# ProPrj_usb__2025-12-14-12-39-50.net
KiCad netlist of a schematic drawn in EasyEDA Pro
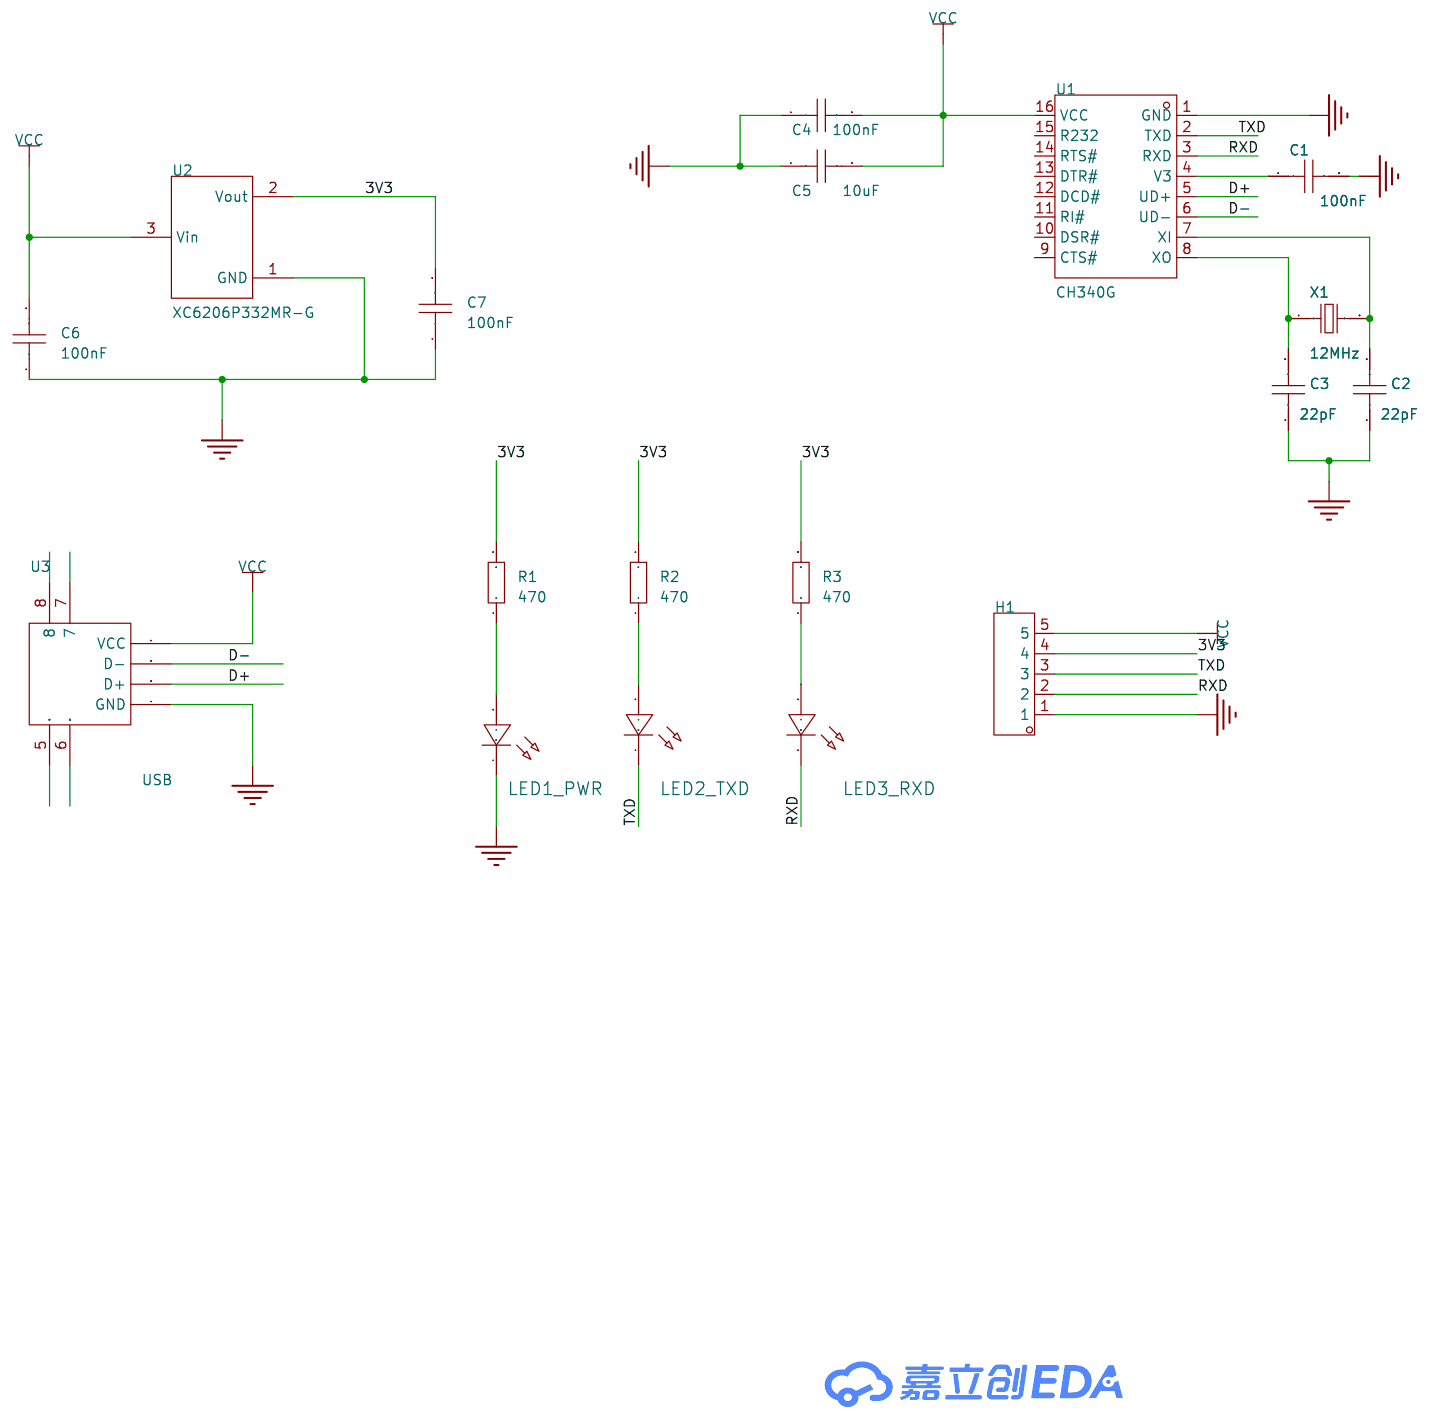
[diagram p0: schematic sheet]

(export (version "E")
  (design (tool "Eeschema 10.0.6"))
  (components
    (comp (ref "C1")
      (value "100nF")
      (footprint "easyedapro:C0603")
      (libsource (lib "easyedapro") (part "Capacitance"))
    )
    (comp (ref "C2")
      (value "22pF")
      (footprint "easyedapro:C0603")
      (libsource (lib "easyedapro") (part "Capacitance"))
    )
    (comp (ref "C3")
      (value "22pF")
      (footprint "easyedapro:C0603")
      (libsource (lib "easyedapro") (part "Capacitance"))
    )
    (comp (ref "C4")
      (value "100nF")
      (footprint "easyedapro:C0603")
      (libsource (lib "easyedapro") (part "Capacitance"))
    )
    (comp (ref "C5")
      (value "10uF")
      (footprint "easyedapro:C0603")
      (libsource (lib "easyedapro") (part "Capacitance"))
    )
    (comp (ref "C6")
      (value "100nF")
      (footprint "easyedapro:C0603")
      (libsource (lib "easyedapro") (part "Capacitance"))
    )
    (comp (ref "C7")
      (value "100nF")
      (footprint "easyedapro:C0603")
      (libsource (lib "easyedapro") (part "Capacitance"))
    )
    (comp (ref "H1")
      (value "~")
      (footprint "easyedapro:HDR-TH_5P-P2.54-V-M")
      (libsource (lib "easyedapro") (part "MTP125-1105S1"))
    )
    (comp (ref "LED1_PWR")
      (value "~")
      (footprint "easyedapro:LED_0603")
      (libsource (lib "easyedapro") (part "LED_R"))
    )
    (comp (ref "LED2_TXD")
      (value "~")
      (footprint "easyedapro:LED_0603")
      (libsource (lib "easyedapro") (part "LED_R"))
    )
    (comp (ref "LED3_RXD")
      (value "~")
      (footprint "easyedapro:LED_0603")
      (libsource (lib "easyedapro") (part "LED_R"))
    )
    (comp (ref "R1") (value "470") (footprint "easyedapro:R0603") (libsource (lib "easyedapro") (part "电阻")))
    (comp (ref "R2") (value "470") (footprint "easyedapro:R0603") (libsource (lib "easyedapro") (part "电阻")))
    (comp (ref "R3") (value "470") (footprint "easyedapro:R0603") (libsource (lib "easyedapro") (part "电阻")))
    (comp (ref "U1")
      (value "CH340G")
      (footprint "easyedapro:SOIC-16_L9.9-W3.9-P1.27-LS6.0-BL")
      (description "应用功能:USB转UART;接口协议:USB 2.0;数据速率:2Mbps;")
      (fields (field (name "Manufacturer") "WCH(南京沁恒)"))
      (libsource (lib "easyedapro") (part "CH340G"))
    )
    (comp (ref "U2")
      (value "XC6206P332MR-G")
      (footprint "easyedapro:SOT-23-3_L2.9-W1.6-P1.90-LS2.8-BR")
      (description "输出类型:固定;工作电压:6V;输出电压:3.3V;输出电流:200mA;电源纹波抑制比(PSRR):-;输出极性:正极;")
      (fields (field (name "Manufacturer") "TOREX(特瑞仕)"))
      (libsource (lib "easyedapro") (part "XC6206P332MR"))
    )
    (comp (ref "U3")
      (value "USB")
      (footprint "easyedapro:USB-SMD_USB_1")
      (libsource (lib "easyedapro") (part "USB"))
    )
    (comp (ref "X1")
      (value "12MHz")
      (footprint "easyedapro:CRYSTAL-SMD_L5.0-W3.2")
      (description "晶振类型:贴片晶振;频率:12MHz;常温频差:±20ppm;负载电容:20pF;频率稳定度:±30ppm;")
      (fields
        (field (name "Manufacturer Part") "XC53G2-12.000-F20LJDT")
        (field (name "Manufacturer") "HCI(杭晶)")
      )
      (libsource (lib "easyedapro") (part "XC53G2-12.000-F20LJDT"))
    )
  )
  (nets
    (net (code "1") (name "/3V3") (class "Default")
      (node (ref "C7") (pin "2") (pinfunction "2_2") (pintype "input"))
      (node (ref "H1") (pin "4") (pinfunction "4_4") (pintype "unspecified"))
      (node (ref "R1") (pin "2") (pinfunction "2_2") (pintype "input"))
      (node (ref "R2") (pin "2") (pinfunction "2_2") (pintype "input"))
      (node (ref "R3") (pin "2") (pinfunction "2_2") (pintype "input"))
      (node (ref "U2") (pin "2") (pinfunction "Vout_2") (pintype "unspecified"))
    )
    (net (code "2") (name "/D+") (class "Default")
      (node (ref "U1") (pin "5") (pinfunction "UD+_5") (pintype "unspecified"))
      (node (ref "U3") (pin "3") (pinfunction "D+_3") (pintype "input"))
    )
    (net (code "3") (name "/D-") (class "Default")
      (node (ref "U1") (pin "6") (pinfunction "UD-_6") (pintype "unspecified"))
      (node (ref "U3") (pin "2") (pinfunction "D-_2") (pintype "input"))
    )
    (net (code "4") (name "/RXD") (class "Default")
      (node (ref "H1") (pin "2") (pinfunction "2_2") (pintype "unspecified"))
      (node (ref "LED3_RXD") (pin "1") (pinfunction "C_1") (pintype "input"))
      (node (ref "U1") (pin "3") (pinfunction "RXD_3") (pintype "unspecified"))
    )
    (net (code "5") (name "/TXD") (class "Default")
      (node (ref "H1") (pin "3") (pinfunction "3_3") (pintype "unspecified"))
      (node (ref "LED2_TXD") (pin "1") (pinfunction "C_1") (pintype "input"))
      (node (ref "U1") (pin "2") (pinfunction "TXD_2") (pintype "unspecified"))
    )
    (net (code "6") (name "GND") (class "Default")
      (node (ref "C1") (pin "2") (pinfunction "2_2") (pintype "input"))
      (node (ref "C2") (pin "1") (pinfunction "1_1") (pintype "input"))
      (node (ref "C3") (pin "1") (pinfunction "1_1") (pintype "input"))
      (node (ref "C4") (pin "1") (pinfunction "1_1") (pintype "input"))
      (node (ref "C5") (pin "1") (pinfunction "1_1") (pintype "input"))
      (node (ref "C6") (pin "1") (pinfunction "1_1") (pintype "input"))
      (node (ref "C7") (pin "1") (pinfunction "1_1") (pintype "input"))
      (node (ref "H1") (pin "1") (pinfunction "1_1") (pintype "unspecified"))
      (node (ref "LED1_PWR") (pin "1") (pinfunction "C_1") (pintype "input"))
      (node (ref "U1") (pin "1") (pinfunction "GND_1") (pintype "unspecified"))
      (node (ref "U2") (pin "1") (pinfunction "GND_1") (pintype "unspecified"))
      (node (ref "U3") (pin "4") (pinfunction "GND_4") (pintype "input"))
    )
    (net (code "7") (name "Net-(LED1_PWR-A)") (class "Default")
      (node (ref "LED1_PWR") (pin "2") (pinfunction "A_2") (pintype "input"))
      (node (ref "R1") (pin "1") (pinfunction "1_1") (pintype "input"))
    )
    (net (code "8") (name "Net-(LED2_TXD-A)") (class "Default")
      (node (ref "LED2_TXD") (pin "2") (pinfunction "A_2") (pintype "input"))
      (node (ref "R2") (pin "1") (pinfunction "1_1") (pintype "input"))
    )
    (net (code "9") (name "Net-(LED3_RXD-A)") (class "Default")
      (node (ref "LED3_RXD") (pin "2") (pinfunction "A_2") (pintype "input"))
      (node (ref "R3") (pin "1") (pinfunction "1_1") (pintype "input"))
    )
    (net (code "10") (name "Net-(U1-V3)") (class "Default")
      (node (ref "C1") (pin "1") (pinfunction "1_1") (pintype "input"))
      (node (ref "U1") (pin "4") (pinfunction "V3_4") (pintype "unspecified"))
    )
    (net (code "11") (name "Net-(U1-XI)") (class "Default")
      (node (ref "C2") (pin "2") (pinfunction "2_2") (pintype "input"))
      (node (ref "U1") (pin "7") (pinfunction "XI_7") (pintype "unspecified"))
      (node (ref "X1") (pin "2") (pinfunction "2_2") (pintype "unspecified"))
    )
    (net (code "12") (name "Net-(U1-XO)") (class "Default")
      (node (ref "C3") (pin "2") (pinfunction "2_2") (pintype "input"))
      (node (ref "U1") (pin "8") (pinfunction "XO_8") (pintype "unspecified"))
      (node (ref "X1") (pin "1") (pinfunction "1_1") (pintype "unspecified"))
    )
    (net (code "13") (name "VCC") (class "Default")
      (node (ref "C4") (pin "2") (pinfunction "2_2") (pintype "input"))
      (node (ref "C5") (pin "2") (pinfunction "2_2") (pintype "input"))
      (node (ref "C6") (pin "2") (pinfunction "2_2") (pintype "input"))
      (node (ref "H1") (pin "5") (pinfunction "5_5") (pintype "unspecified"))
      (node (ref "U1") (pin "16") (pinfunction "VCC_16") (pintype "unspecified"))
      (node (ref "U2") (pin "3") (pinfunction "Vin_3") (pintype "unspecified"))
      (node (ref "U3") (pin "1") (pinfunction "VCC_1") (pintype "input"))
    )
    (net (code "14") (name "unconnected-(U1-CTS#-Pad9)") (class "Default")
      (node (ref "U1") (pin "9") (pinfunction "CTS#_9") (pintype "unspecified"))
    )
    (net (code "15") (name "unconnected-(U1-DCD#-Pad12)") (class "Default")
      (node (ref "U1") (pin "12") (pinfunction "DCD#_12") (pintype "unspecified"))
    )
    (net (code "16") (name "unconnected-(U1-DSR#-Pad10)") (class "Default")
      (node (ref "U1") (pin "10") (pinfunction "DSR#_10") (pintype "unspecified"))
    )
    (net (code "17") (name "unconnected-(U1-DTR#-Pad13)") (class "Default")
      (node (ref "U1") (pin "13") (pinfunction "DTR#_13") (pintype "unspecified"))
    )
    (net (code "18") (name "unconnected-(U1-R232-Pad15)") (class "Default")
      (node (ref "U1") (pin "15") (pinfunction "R232_15") (pintype "unspecified"))
    )
    (net (code "19") (name "unconnected-(U1-RI#-Pad11)") (class "Default")
      (node (ref "U1") (pin "11") (pinfunction "RI#_11") (pintype "unspecified"))
    )
    (net (code "20") (name "unconnected-(U1-RTS#-Pad14)") (class "Default")
      (node (ref "U1") (pin "14") (pinfunction "RTS#_14") (pintype "unspecified"))
    )
    (net (code "21") (name "unconnected-(U3-Pad7)") (class "Default")
      (node (ref "U3") (pin "7") (pinfunction "7_7") (pintype "unspecified"))
    )
    (net (code "22") (name "unconnected-(U3-Pad8)") (class "Default")
      (node (ref "U3") (pin "8") (pinfunction "8_8") (pintype "unspecified"))
    )
    (net (code "23") (name "unconnected-(U3-SH1-Pad5)") (class "Default")
      (node (ref "U3") (pin "5") (pinfunction "SH1_5") (pintype "unspecified"))
    )
    (net (code "24") (name "unconnected-(U3-SH2-Pad6)") (class "Default")
      (node (ref "U3") (pin "6") (pinfunction "SH2_6") (pintype "unspecified"))
    )
  )
)
